# Power_Supply.net
KiCad netlist of a schematic drawn in Altium Designer
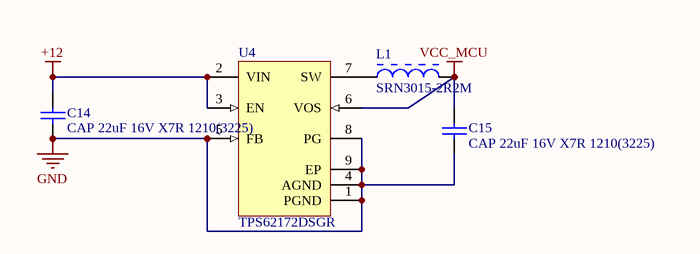
[diagram p0: Power_Supply.SchDoc]

(export (version "E")
  (design (tool "Eeschema 10.0.6"))
  (components
    (comp (ref "C14")
      (value "CAP 22uF 16V X7R 1210(3225)")
      (footprint "CAPC1210(3225)280_L")
      (description "CAP 22uF 16V ±10% 1210 (3225 Metric) Thickness 2.8mm SMD")
      (fields (field (name "TOLERANCE") "Â±10%"))
      (libsource (lib "Altium Content Vault") (part "CAP"))
    )
    (comp (ref "C15")
      (value "CAP 22uF 16V X7R 1210(3225)")
      (footprint "CAPC1210(3225)280_L")
      (description "CAP 22uF 16V ±10% 1210 (3225 Metric) Thickness 2.8mm SMD")
      (fields (field (name "TOLERANCE") "Â±10%"))
      (libsource (lib "Altium Content Vault") (part "CAP"))
    )
    (comp (ref "L1")
      (value "SRN3015-2R2M")
      (footprint "BOUR-SRN3015-2_V")
      (fields (field (name "MANUFACTURER") "Bourns"))
      (libsource (lib "Altium Content Vault") (part "BOUR-IND-2A"))
    )
    (comp (ref "U4")
      (value "TPS62172DSGR")
      (footprint "DSG8-1600X900TP")
      (fields (field (name "MANUFACTURER") "Texas Instruments"))
      (libsource (lib "Texas_Instruments_TPS62172DSGR") (part "TPS62172DSGR"))
    )
  )
  (nets
    (net (code "1") (name "+12") (class "Default")
      (node (ref "C14") (pin "2") (pinfunction "2_2") (pintype "passive"))
      (node (ref "U4") (pin "2") (pinfunction "VIN_2") (pintype "power_in"))
      (node (ref "U4") (pin "3") (pinfunction "EN_3") (pintype "input"))
    )
    (net (code "2") (name "GND") (class "Default")
      (node (ref "C14") (pin "1") (pinfunction "1_1") (pintype "passive"))
      (node (ref "C15") (pin "1") (pinfunction "1_1") (pintype "passive"))
      (node (ref "U4") (pin "1") (pinfunction "PGND_1") (pintype "power_in"))
      (node (ref "U4") (pin "4") (pinfunction "AGND_4") (pintype "power_in"))
      (node (ref "U4") (pin "5") (pinfunction "FB_5") (pintype "input"))
      (node (ref "U4") (pin "8") (pinfunction "PG_8") (pintype "passive"))
      (node (ref "U4") (pin "9") (pinfunction "EP_9") (pintype "power_in"))
    )
    (net (code "3") (name "Net-(U4-SW)") (class "Default")
      (node (ref "L1") (pin "1") (pinfunction "1_1") (pintype "passive"))
      (node (ref "U4") (pin "7") (pinfunction "SW_7") (pintype "power_in"))
    )
    (net (code "4") (name "VCC_MCU") (class "Default")
      (node (ref "C15") (pin "2") (pinfunction "2_2") (pintype "passive"))
      (node (ref "L1") (pin "2") (pinfunction "2_2") (pintype "passive"))
      (node (ref "U4") (pin "6") (pinfunction "VOS_6") (pintype "input"))
    )
  )
)
